# mainboard.net
KiCad netlist of a schematic drawn in EAGLE
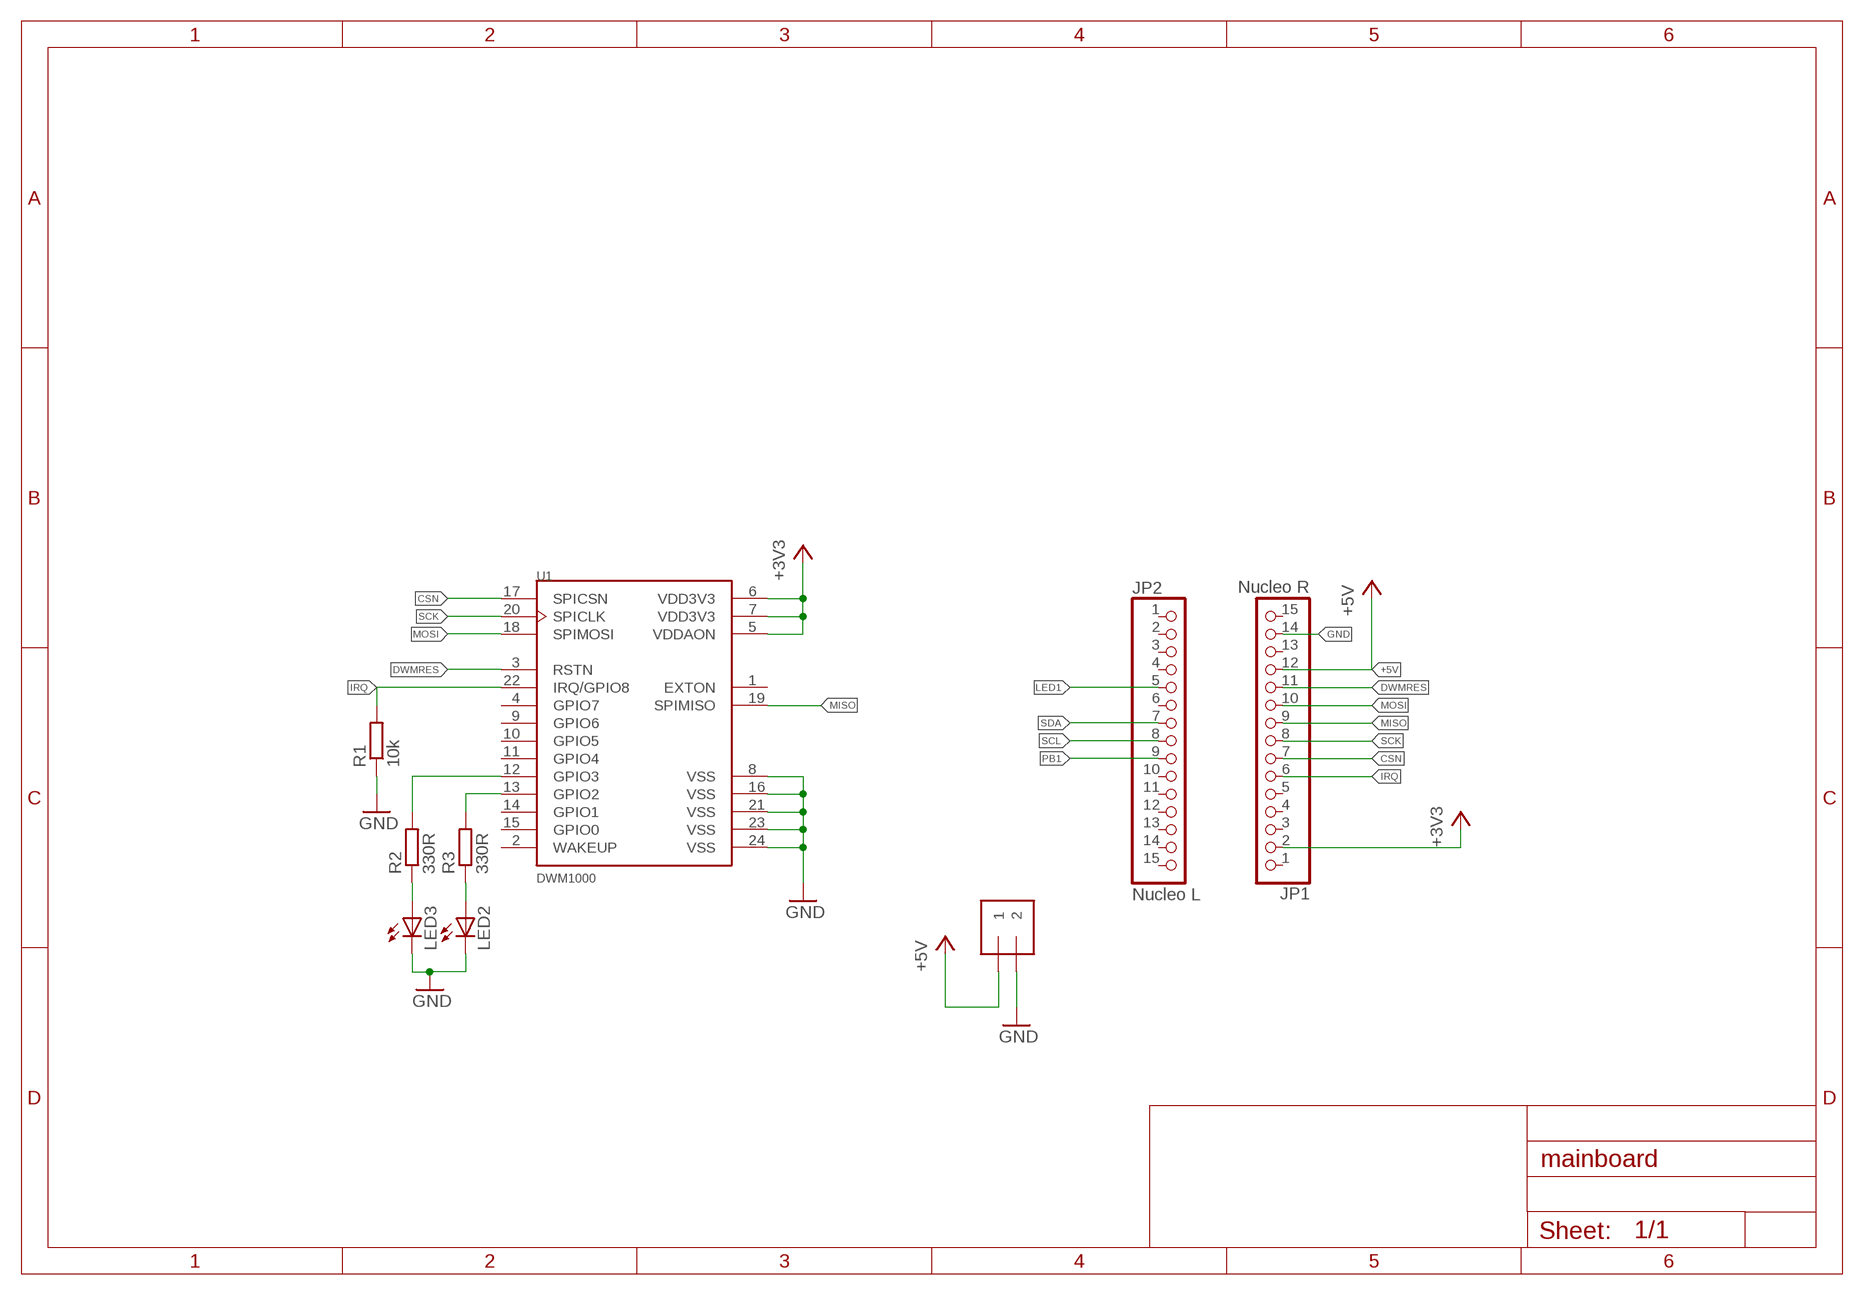
[diagram p0: schematic, sheet 1]

(export (version "E")
  (design (tool "Eeschema 10.0.6"))
  (components
    (comp (ref "J1")
      (value "1X2-3.5MM")
      (footprint "eagle-import:1X2-3.5MM")
      (libsource (lib "eagle-import") (part "1X2-3.5MM"))
    )
    (comp (ref "JP1")
      (value "Nucleo R")
      (footprint "eagle-import:1X15")
      (libsource (lib "eagle-import") (part "PINHD-1X15"))
    )
    (comp (ref "JP2")
      (value "Nucleo L")
      (footprint "eagle-import:1X15")
      (libsource (lib "eagle-import") (part "PINHD-1X15"))
    )
    (comp (ref "LED2")
      (value "LEDSML0603")
      (footprint "eagle-import:SML0603")
      (libsource (lib "eagle-import") (part "LEDSML0603"))
    )
    (comp (ref "LED3")
      (value "LEDSML0603")
      (footprint "eagle-import:SML0603")
      (libsource (lib "eagle-import") (part "LEDSML0603"))
    )
    (comp (ref "R1")
      (value "10k")
      (footprint "eagle-import:R0603")
      (libsource (lib "eagle-import") (part "R-EU_R0603"))
    )
    (comp (ref "R2")
      (value "330R")
      (footprint "eagle-import:R0603")
      (libsource (lib "eagle-import") (part "R-EU_R0603"))
    )
    (comp (ref "R3")
      (value "330R")
      (footprint "eagle-import:R0603")
      (libsource (lib "eagle-import") (part "R-EU_R0603"))
    )
    (comp (ref "U1")
      (value "DWM1000")
      (footprint "eagle-import:XCVR_DWM1000")
      (libsource (lib "eagle-import") (part "DWM1000"))
    )
  )
  (nets
    (net (code "1") (name "+3V3") (class "Default")
      (node (ref "JP1") (pin "2") (pinfunction "2_2") (pintype "passive"))
      (node (ref "U1") (pin "5") (pinfunction "VDDAON_5") (pintype "power_in"))
      (node (ref "U1") (pin "6") (pinfunction "VDD3V3_6") (pintype "power_in"))
      (node (ref "U1") (pin "7") (pinfunction "VDD3V3_7") (pintype "power_in"))
    )
    (net (code "2") (name "+5V") (class "Default")
      (node (ref "J1") (pin "1") (pinfunction "1_1") (pintype "passive"))
      (node (ref "JP1") (pin "12") (pinfunction "12_12") (pintype "passive"))
    )
    (net (code "3") (name "CSN") (class "Default")
      (node (ref "JP1") (pin "7") (pinfunction "7_7") (pintype "passive"))
      (node (ref "U1") (pin "17") (pinfunction "SPICSN_17") (pintype "input"))
    )
    (net (code "4") (name "DWMRES") (class "Default")
      (node (ref "JP1") (pin "11") (pinfunction "11_11") (pintype "passive"))
      (node (ref "U1") (pin "3") (pinfunction "RSTN_3") (pintype "bidirectional"))
    )
    (net (code "5") (name "GND") (class "Default")
      (node (ref "J1") (pin "2") (pinfunction "2_2") (pintype "passive"))
      (node (ref "JP1") (pin "14") (pinfunction "14_14") (pintype "passive"))
      (node (ref "LED2") (pin "C") (pinfunction "C_C") (pintype "passive"))
      (node (ref "LED3") (pin "C") (pinfunction "C_C") (pintype "passive"))
      (node (ref "R1") (pin "1") (pinfunction "1_1") (pintype "passive"))
      (node (ref "U1") (pin "16") (pinfunction "VSS_16") (pintype "power_in"))
      (node (ref "U1") (pin "21") (pinfunction "VSS_21") (pintype "power_in"))
      (node (ref "U1") (pin "23") (pinfunction "VSS_23") (pintype "power_in"))
      (node (ref "U1") (pin "24") (pinfunction "VSS_24") (pintype "power_in"))
      (node (ref "U1") (pin "8") (pinfunction "VSS_8") (pintype "power_in"))
    )
    (net (code "6") (name "IRQ") (class "Default")
      (node (ref "JP1") (pin "6") (pinfunction "6_6") (pintype "passive"))
      (node (ref "R1") (pin "2") (pinfunction "2_2") (pintype "passive"))
      (node (ref "U1") (pin "22") (pinfunction "IRQ/GPIO8_22") (pintype "bidirectional"))
    )
    (net (code "7") (name "LED1") (class "Default")
      (node (ref "JP2") (pin "5") (pinfunction "5_5") (pintype "passive"))
    )
    (net (code "8") (name "MISO") (class "Default")
      (node (ref "JP1") (pin "9") (pinfunction "9_9") (pintype "passive"))
      (node (ref "U1") (pin "19") (pinfunction "SPIMISO_19") (pintype "output"))
    )
    (net (code "9") (name "MOSI") (class "Default")
      (node (ref "JP1") (pin "10") (pinfunction "10_10") (pintype "passive"))
      (node (ref "U1") (pin "18") (pinfunction "SPIMOSI_18") (pintype "input"))
    )
    (net (code "10") (name "Net-(LED2-PadA)") (class "Default")
      (node (ref "LED2") (pin "A") (pinfunction "A_A") (pintype "passive"))
      (node (ref "R3") (pin "1") (pinfunction "1_1") (pintype "passive"))
    )
    (net (code "11") (name "Net-(LED3-PadA)") (class "Default")
      (node (ref "LED3") (pin "A") (pinfunction "A_A") (pintype "passive"))
      (node (ref "R2") (pin "1") (pinfunction "1_1") (pintype "passive"))
    )
    (net (code "12") (name "Net-(U1-GPIO2)") (class "Default")
      (node (ref "R3") (pin "2") (pinfunction "2_2") (pintype "passive"))
      (node (ref "U1") (pin "13") (pinfunction "GPIO2_13") (pintype "bidirectional"))
    )
    (net (code "13") (name "Net-(U1-GPIO3)") (class "Default")
      (node (ref "R2") (pin "2") (pinfunction "2_2") (pintype "passive"))
      (node (ref "U1") (pin "12") (pinfunction "GPIO3_12") (pintype "bidirectional"))
    )
    (net (code "14") (name "PB1") (class "Default")
      (node (ref "JP2") (pin "9") (pinfunction "9_9") (pintype "passive"))
    )
    (net (code "15") (name "SCK") (class "Default")
      (node (ref "JP1") (pin "8") (pinfunction "8_8") (pintype "passive"))
      (node (ref "U1") (pin "20") (pinfunction "SPICLK_20") (pintype "input"))
    )
    (net (code "16") (name "SCL") (class "Default")
      (node (ref "JP2") (pin "8") (pinfunction "8_8") (pintype "passive"))
    )
    (net (code "17") (name "SDA") (class "Default")
      (node (ref "JP2") (pin "7") (pinfunction "7_7") (pintype "passive"))
    )
    (net (code "18") (name "unconnected-(JP1-Pad1)") (class "Default")
      (node (ref "JP1") (pin "1") (pinfunction "1_1") (pintype "passive"))
    )
    (net (code "19") (name "unconnected-(JP1-Pad3)") (class "Default")
      (node (ref "JP1") (pin "3") (pinfunction "3_3") (pintype "passive"))
    )
    (net (code "20") (name "unconnected-(JP1-Pad4)") (class "Default")
      (node (ref "JP1") (pin "4") (pinfunction "4_4") (pintype "passive"))
    )
    (net (code "21") (name "unconnected-(JP1-Pad5)") (class "Default")
      (node (ref "JP1") (pin "5") (pinfunction "5_5") (pintype "passive"))
    )
    (net (code "22") (name "unconnected-(JP1-Pad13)") (class "Default")
      (node (ref "JP1") (pin "13") (pinfunction "13_13") (pintype "passive"))
    )
    (net (code "23") (name "unconnected-(JP1-Pad15)") (class "Default")
      (node (ref "JP1") (pin "15") (pinfunction "15_15") (pintype "passive"))
    )
    (net (code "24") (name "unconnected-(JP2-Pad1)") (class "Default")
      (node (ref "JP2") (pin "1") (pinfunction "1_1") (pintype "passive"))
    )
    (net (code "25") (name "unconnected-(JP2-Pad2)") (class "Default")
      (node (ref "JP2") (pin "2") (pinfunction "2_2") (pintype "passive"))
    )
    (net (code "26") (name "unconnected-(JP2-Pad3)") (class "Default")
      (node (ref "JP2") (pin "3") (pinfunction "3_3") (pintype "passive"))
    )
    (net (code "27") (name "unconnected-(JP2-Pad4)") (class "Default")
      (node (ref "JP2") (pin "4") (pinfunction "4_4") (pintype "passive"))
    )
    (net (code "28") (name "unconnected-(JP2-Pad6)") (class "Default")
      (node (ref "JP2") (pin "6") (pinfunction "6_6") (pintype "passive"))
    )
    (net (code "29") (name "unconnected-(JP2-Pad10)") (class "Default")
      (node (ref "JP2") (pin "10") (pinfunction "10_10") (pintype "passive"))
    )
    (net (code "30") (name "unconnected-(JP2-Pad11)") (class "Default")
      (node (ref "JP2") (pin "11") (pinfunction "11_11") (pintype "passive"))
    )
    (net (code "31") (name "unconnected-(JP2-Pad12)") (class "Default")
      (node (ref "JP2") (pin "12") (pinfunction "12_12") (pintype "passive"))
    )
    (net (code "32") (name "unconnected-(JP2-Pad13)") (class "Default")
      (node (ref "JP2") (pin "13") (pinfunction "13_13") (pintype "passive"))
    )
    (net (code "33") (name "unconnected-(JP2-Pad14)") (class "Default")
      (node (ref "JP2") (pin "14") (pinfunction "14_14") (pintype "passive"))
    )
    (net (code "34") (name "unconnected-(JP2-Pad15)") (class "Default")
      (node (ref "JP2") (pin "15") (pinfunction "15_15") (pintype "passive"))
    )
    (net (code "35") (name "unconnected-(U1-EXTON-Pad1)") (class "Default")
      (node (ref "U1") (pin "1") (pinfunction "EXTON_1") (pintype "output"))
    )
    (net (code "36") (name "unconnected-(U1-GPIO0-Pad15)") (class "Default")
      (node (ref "U1") (pin "15") (pinfunction "GPIO0_15") (pintype "bidirectional"))
    )
    (net (code "37") (name "unconnected-(U1-GPIO1-Pad14)") (class "Default")
      (node (ref "U1") (pin "14") (pinfunction "GPIO1_14") (pintype "bidirectional"))
    )
    (net (code "38") (name "unconnected-(U1-GPIO4-Pad11)") (class "Default")
      (node (ref "U1") (pin "11") (pinfunction "GPIO4_11") (pintype "bidirectional"))
    )
    (net (code "39") (name "unconnected-(U1-GPIO5-Pad10)") (class "Default")
      (node (ref "U1") (pin "10") (pinfunction "GPIO5_10") (pintype "bidirectional"))
    )
    (net (code "40") (name "unconnected-(U1-GPIO6-Pad9)") (class "Default")
      (node (ref "U1") (pin "9") (pinfunction "GPIO6_9") (pintype "bidirectional"))
    )
    (net (code "41") (name "unconnected-(U1-GPIO7-Pad4)") (class "Default")
      (node (ref "U1") (pin "4") (pinfunction "GPIO7_4") (pintype "bidirectional"))
    )
    (net (code "42") (name "unconnected-(U1-WAKEUP-Pad2)") (class "Default")
      (node (ref "U1") (pin "2") (pinfunction "WAKEUP_2") (pintype "bidirectional"))
    )
  )
)
